# ownduino-metaboard2.net
KiCad netlist of a schematic drawn in EAGLE
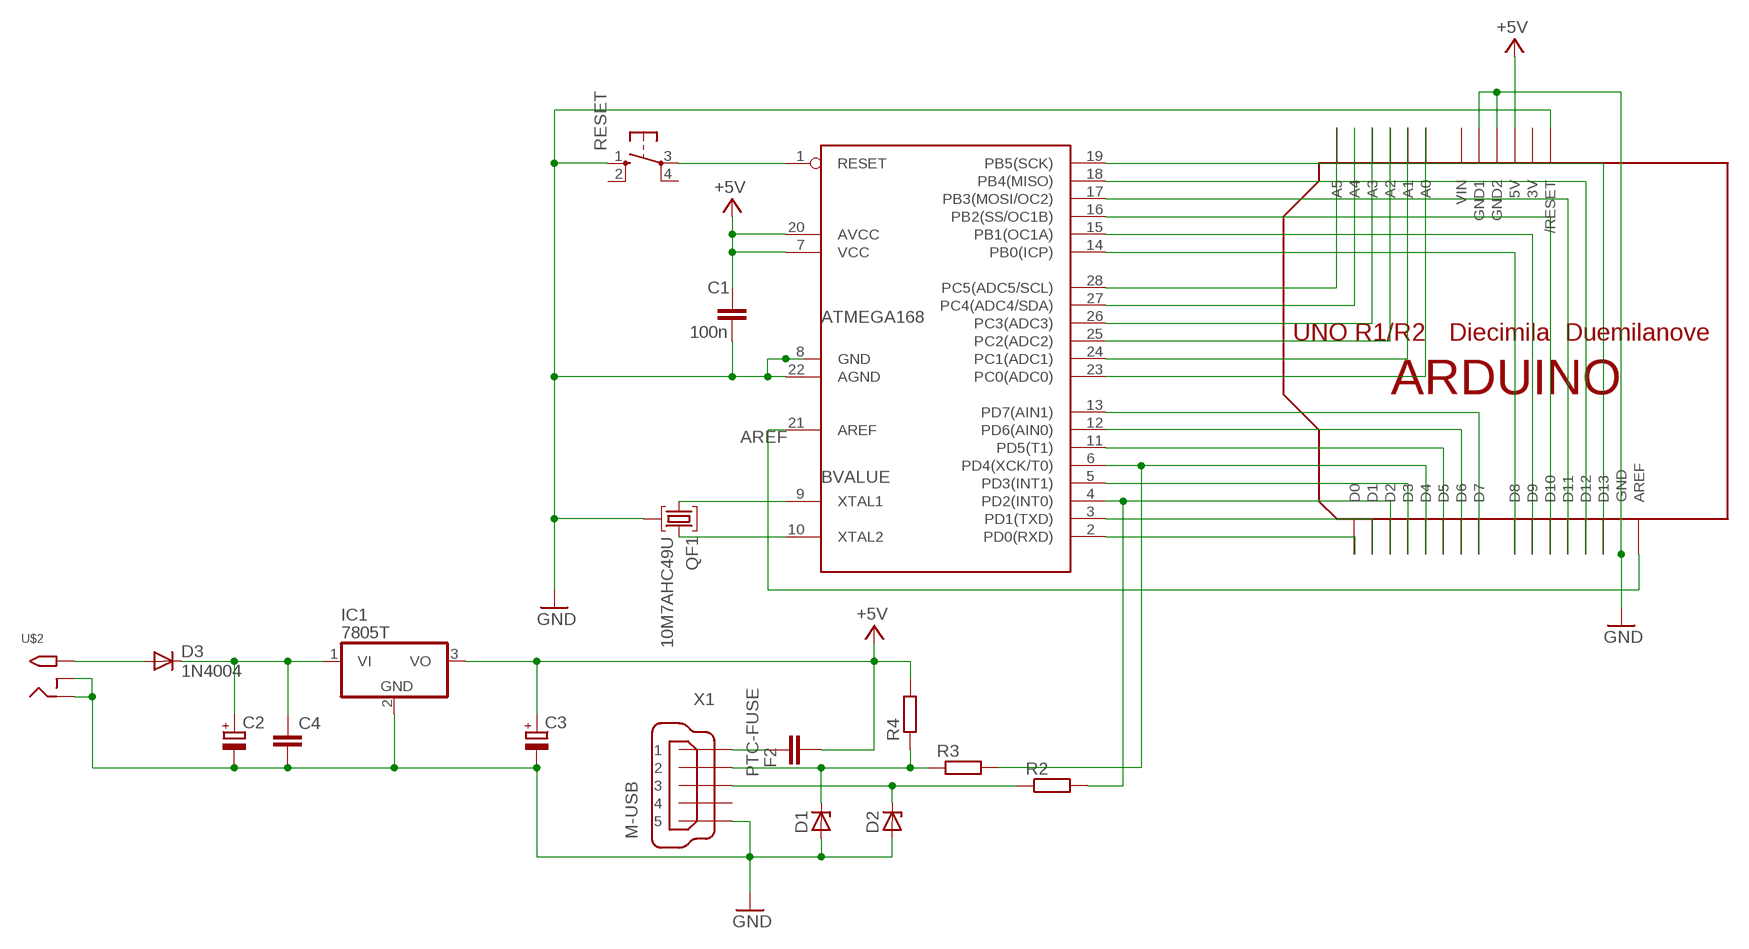
[diagram p0: schematic, sheet 1]

(export (version "E")
  (design (tool "Eeschema 10.0.6"))
  (components
    (comp (ref "BVALUE")
      (value "ATMEGA168")
      (footprint "eagle-import:DIL28-3")
      (libsource (lib "eagle-import") (part "MEGA8-P"))
    )
    (comp (ref "C1")
      (value "100n")
      (footprint "eagle-import:C025-024X044")
      (libsource (lib "eagle-import") (part "C-EU025-024X044"))
    )
    (comp (ref "C2")
      (value "CPOL-EUE5-8.5")
      (footprint "eagle-import:E5-8,5")
      (libsource (lib "eagle-import") (part "CPOL-EUE5-8.5"))
    )
    (comp (ref "C3")
      (value "CPOL-EUE5-8.5")
      (footprint "eagle-import:E5-8,5")
      (libsource (lib "eagle-import") (part "CPOL-EUE5-8.5"))
    )
    (comp (ref "C4")
      (value "C-EU025-025X050")
      (footprint "eagle-import:C025-025X050")
      (libsource (lib "eagle-import") (part "C-EU025-025X050"))
    )
    (comp (ref "D1")
      (value "ZENER-DIODEZD-7.5")
      (footprint "eagle-import:ZDIO-7.5")
      (libsource (lib "eagle-import") (part "ZENER-DIODEZD-7.5"))
    )
    (comp (ref "D2")
      (value "ZENER-DIODEZD-5")
      (footprint "eagle-import:ZDIO-5")
      (libsource (lib "eagle-import") (part "ZENER-DIODEZD-5"))
    )
    (comp (ref "D3")
      (value "1N4004")
      (footprint "eagle-import:DO41-10")
      (libsource (lib "eagle-import") (part "1N4004"))
    )
    (comp (ref "F2")
      (value "PTC-FUSE")
      (footprint "eagle-import:C025_050-025X075")
      (libsource (lib "eagle-import") (part "C-EU025_050-025X075"))
    )
    (comp (ref "IC1")
      (value "7805T")
      (footprint "eagle-import:TO220H")
      (libsource (lib "eagle-import") (part "78T05"))
    )
    (comp (ref "QF1")
      (value "10M7AHC49U")
      (footprint "eagle-import:HC49U")
      (libsource (lib "eagle-import") (part "10MAHC49U7"))
    )
    (comp (ref "R2")
      (value "R-EU_0207/12")
      (footprint "eagle-import:0207_12")
      (libsource (lib "eagle-import") (part "R-EU_0207/12"))
    )
    (comp (ref "R3")
      (value "R-EU_0207/10")
      (footprint "eagle-import:0207_10")
      (libsource (lib "eagle-import") (part "R-EU_0207/10"))
    )
    (comp (ref "R4")
      (value "R-EU_0207/10")
      (footprint "eagle-import:0207_10")
      (libsource (lib "eagle-import") (part "R-EU_0207/10"))
    )
    (comp (ref "RESET")
      (value "10-XX")
      (footprint "eagle-import:B3F-10XX")
      (libsource (lib "eagle-import") (part "10-XX"))
    )
    (comp (ref "U$1")
      (value "ARDUINOUNO")
      (footprint "eagle-import:ARDUINO")
      (libsource (lib "eagle-import") (part "ARDUINOUNO"))
    )
    (comp (ref "U$2")
      (value "2.1MMJACKTHM")
      (footprint "eagle-import:PJ-102A")
      (libsource (lib "eagle-import") (part "2.1MMJACKTHM"))
    )
    (comp (ref "X1")
      (value "M-USB")
      (footprint "eagle-import:32005-601")
      (libsource (lib "eagle-import") (part "MINI-USB_SHIELD5P2-32005-601"))
    )
  )
  (nets
    (net (code "1") (name "+5V") (class "Default")
      (node (ref "BVALUE") (pin "20") (pinfunction "AVCC_20") (pintype "bidirectional"))
      (node (ref "BVALUE") (pin "7") (pinfunction "VCC_7") (pintype "bidirectional"))
      (node (ref "C1") (pin "1") (pinfunction "1_1") (pintype "passive"))
      (node (ref "C3") (pin "+") (pinfunction "+_+") (pintype "passive"))
      (node (ref "F2") (pin "1") (pinfunction "1_1") (pintype "passive"))
      (node (ref "IC1") (pin "3") (pinfunction "VO_3") (pintype "passive"))
      (node (ref "R4") (pin "2") (pinfunction "2_2") (pintype "passive"))
      (node (ref "U$1") (pin "5V") (pinfunction "5V_5V") (pintype "power_in"))
    )
    (net (code "2") (name "/3V") (class "Default")
      (node (ref "U$1") (pin "3V") (pinfunction "3V_3V") (pintype "power_in"))
    )
    (net (code "3") (name "/AREF") (class "Default")
      (node (ref "BVALUE") (pin "21") (pinfunction "AREF_21") (pintype "bidirectional"))
      (node (ref "U$1") (pin "AREF") (pinfunction "AREF_AREF") (pintype "bidirectional"))
    )
    (net (code "4") (name "/VIN") (class "Default")
      (node (ref "U$1") (pin "VIN") (pinfunction "VIN_VIN") (pintype "power_in"))
    )
    (net (code "5") (name "GND") (class "Default")
      (node (ref "BVALUE") (pin "22") (pinfunction "AGND_22") (pintype "bidirectional"))
      (node (ref "BVALUE") (pin "8") (pinfunction "GND_8") (pintype "bidirectional"))
      (node (ref "C1") (pin "2") (pinfunction "2_2") (pintype "passive"))
      (node (ref "C2") (pin "-") (pinfunction "-_-") (pintype "passive"))
      (node (ref "C3") (pin "-") (pinfunction "-_-") (pintype "passive"))
      (node (ref "C4") (pin "2") (pinfunction "2_2") (pintype "passive"))
      (node (ref "D1") (pin "A") (pinfunction "A_A") (pintype "passive"))
      (node (ref "D2") (pin "A") (pinfunction "A_A") (pintype "passive"))
      (node (ref "IC1") (pin "2") (pinfunction "GND_2") (pintype "passive"))
      (node (ref "QF1") (pin "2") (pinfunction "2_2") (pintype "passive"))
      (node (ref "RESET") (pin "1") (pinfunction "S_1") (pintype "passive"))
      (node (ref "U$1") (pin "GND") (pinfunction "GND_GND") (pintype "power_in"))
      (node (ref "U$1") (pin "GND1") (pinfunction "GND1_GND1") (pintype "power_in"))
      (node (ref "U$1") (pin "GND2") (pinfunction "GND2_GND2") (pintype "power_in"))
      (node (ref "U$1") (pin "RESET") (pinfunction "/RESET_RESET") (pintype "bidirectional"))
      (node (ref "U$2") (pin "RING") (pinfunction "RING_RING") (pintype "bidirectional"))
      (node (ref "U$2") (pin "RING_SW") (pinfunction "RING_SW_RING_SW") (pintype "bidirectional"))
      (node (ref "X1") (pin "5") (pinfunction "5_5") (pintype "passive"))
    )
    (net (code "6") (name "Net-(BVALUE-PB0(ICP))") (class "Default")
      (node (ref "BVALUE") (pin "14") (pinfunction "PB0(ICP)_14") (pintype "bidirectional"))
      (node (ref "U$1") (pin "D8") (pinfunction "D8_D8") (pintype "bidirectional"))
    )
    (net (code "7") (name "Net-(BVALUE-PB1(OC1A))") (class "Default")
      (node (ref "BVALUE") (pin "15") (pinfunction "PB1(OC1A)_15") (pintype "bidirectional"))
      (node (ref "U$1") (pin "D9") (pinfunction "D9_D9") (pintype "bidirectional"))
    )
    (net (code "8") (name "Net-(BVALUE-PB2(SS{slash}OC1B))") (class "Default")
      (node (ref "BVALUE") (pin "16") (pinfunction "PB2(SS/OC1B)_16") (pintype "bidirectional"))
      (node (ref "U$1") (pin "D10") (pinfunction "D10_D10") (pintype "bidirectional"))
    )
    (net (code "9") (name "Net-(BVALUE-PB3(MOSI{slash}OC2))") (class "Default")
      (node (ref "BVALUE") (pin "17") (pinfunction "PB3(MOSI/OC2)_17") (pintype "bidirectional"))
      (node (ref "U$1") (pin "D11") (pinfunction "D11_D11") (pintype "bidirectional"))
    )
    (net (code "10") (name "Net-(BVALUE-PB4(MISO))") (class "Default")
      (node (ref "BVALUE") (pin "18") (pinfunction "PB4(MISO)_18") (pintype "bidirectional"))
      (node (ref "U$1") (pin "D12") (pinfunction "D12_D12") (pintype "bidirectional"))
    )
    (net (code "11") (name "Net-(BVALUE-PB5(SCK))") (class "Default")
      (node (ref "BVALUE") (pin "19") (pinfunction "PB5(SCK)_19") (pintype "bidirectional"))
      (node (ref "U$1") (pin "D13") (pinfunction "D13_D13") (pintype "bidirectional"))
    )
    (net (code "12") (name "Net-(BVALUE-PC0(ADC0))") (class "Default")
      (node (ref "BVALUE") (pin "23") (pinfunction "PC0(ADC0)_23") (pintype "bidirectional"))
      (node (ref "U$1") (pin "A0") (pinfunction "A0_A0") (pintype "bidirectional"))
    )
    (net (code "13") (name "Net-(BVALUE-PC1(ADC1))") (class "Default")
      (node (ref "BVALUE") (pin "24") (pinfunction "PC1(ADC1)_24") (pintype "bidirectional"))
      (node (ref "U$1") (pin "A1") (pinfunction "A1_A1") (pintype "bidirectional"))
    )
    (net (code "14") (name "Net-(BVALUE-PC2(ADC2))") (class "Default")
      (node (ref "BVALUE") (pin "25") (pinfunction "PC2(ADC2)_25") (pintype "bidirectional"))
      (node (ref "U$1") (pin "A2") (pinfunction "A2_A2") (pintype "bidirectional"))
    )
    (net (code "15") (name "Net-(BVALUE-PC3(ADC3))") (class "Default")
      (node (ref "BVALUE") (pin "26") (pinfunction "PC3(ADC3)_26") (pintype "bidirectional"))
      (node (ref "U$1") (pin "A3") (pinfunction "A3_A3") (pintype "bidirectional"))
    )
    (net (code "16") (name "Net-(BVALUE-PC4(ADC4{slash}SDA))") (class "Default")
      (node (ref "BVALUE") (pin "27") (pinfunction "PC4(ADC4/SDA)_27") (pintype "bidirectional"))
      (node (ref "U$1") (pin "A4") (pinfunction "A4_A4") (pintype "bidirectional"))
    )
    (net (code "17") (name "Net-(BVALUE-PC5(ADC5{slash}SCL))") (class "Default")
      (node (ref "BVALUE") (pin "28") (pinfunction "PC5(ADC5/SCL)_28") (pintype "bidirectional"))
      (node (ref "U$1") (pin "A5") (pinfunction "A5_A5") (pintype "bidirectional"))
    )
    (net (code "18") (name "Net-(BVALUE-PD0(RXD))") (class "Default")
      (node (ref "BVALUE") (pin "2") (pinfunction "PD0(RXD)_2") (pintype "bidirectional"))
      (node (ref "U$1") (pin "D0") (pinfunction "D0_D0") (pintype "bidirectional"))
    )
    (net (code "19") (name "Net-(BVALUE-PD1(TXD))") (class "Default")
      (node (ref "BVALUE") (pin "3") (pinfunction "PD1(TXD)_3") (pintype "bidirectional"))
      (node (ref "U$1") (pin "D1") (pinfunction "D1_D1") (pintype "bidirectional"))
    )
    (net (code "20") (name "Net-(BVALUE-PD2(INT0))") (class "Default")
      (node (ref "BVALUE") (pin "4") (pinfunction "PD2(INT0)_4") (pintype "bidirectional"))
      (node (ref "R2") (pin "2") (pinfunction "2_2") (pintype "passive"))
      (node (ref "U$1") (pin "D2") (pinfunction "D2_D2") (pintype "bidirectional"))
    )
    (net (code "21") (name "Net-(BVALUE-PD3(INT1))") (class "Default")
      (node (ref "BVALUE") (pin "5") (pinfunction "PD3(INT1)_5") (pintype "bidirectional"))
      (node (ref "U$1") (pin "D3") (pinfunction "D3_D3") (pintype "bidirectional"))
    )
    (net (code "22") (name "Net-(BVALUE-PD4(XCK{slash}T0))") (class "Default")
      (node (ref "BVALUE") (pin "6") (pinfunction "PD4(XCK/T0)_6") (pintype "bidirectional"))
      (node (ref "R3") (pin "2") (pinfunction "2_2") (pintype "passive"))
      (node (ref "U$1") (pin "D4") (pinfunction "D4_D4") (pintype "bidirectional"))
    )
    (net (code "23") (name "Net-(BVALUE-PD5(T1))") (class "Default")
      (node (ref "BVALUE") (pin "11") (pinfunction "PD5(T1)_11") (pintype "bidirectional"))
      (node (ref "U$1") (pin "D5") (pinfunction "D5_D5") (pintype "bidirectional"))
    )
    (net (code "24") (name "Net-(BVALUE-PD6(AIN0))") (class "Default")
      (node (ref "BVALUE") (pin "12") (pinfunction "PD6(AIN0)_12") (pintype "bidirectional"))
      (node (ref "U$1") (pin "D6") (pinfunction "D6_D6") (pintype "bidirectional"))
    )
    (net (code "25") (name "Net-(BVALUE-PD7(AIN1))") (class "Default")
      (node (ref "BVALUE") (pin "13") (pinfunction "PD7(AIN1)_13") (pintype "bidirectional"))
      (node (ref "U$1") (pin "D7") (pinfunction "D7_D7") (pintype "bidirectional"))
    )
    (net (code "26") (name "Net-(BVALUE-RESET)") (class "Default")
      (node (ref "BVALUE") (pin "1") (pinfunction "RESET_1") (pintype "bidirectional"))
      (node (ref "RESET") (pin "3") (pinfunction "P_3") (pintype "passive"))
    )
    (net (code "27") (name "Net-(BVALUE-XTAL1)") (class "Default")
      (node (ref "BVALUE") (pin "9") (pinfunction "XTAL1_9") (pintype "bidirectional"))
      (node (ref "QF1") (pin "1") (pinfunction "1_1") (pintype "passive"))
    )
    (net (code "28") (name "Net-(BVALUE-XTAL2)") (class "Default")
      (node (ref "BVALUE") (pin "10") (pinfunction "XTAL2_10") (pintype "bidirectional"))
      (node (ref "QF1") (pin "3") (pinfunction "3_3") (pintype "passive"))
    )
    (net (code "29") (name "Net-(D1-PadC)") (class "Default")
      (node (ref "D1") (pin "C") (pinfunction "C_C") (pintype "passive"))
      (node (ref "R3") (pin "1") (pinfunction "1_1") (pintype "passive"))
      (node (ref "R4") (pin "1") (pinfunction "1_1") (pintype "passive"))
      (node (ref "X1") (pin "2") (pinfunction "2_2") (pintype "passive"))
    )
    (net (code "30") (name "Net-(D2-PadC)") (class "Default")
      (node (ref "D2") (pin "C") (pinfunction "C_C") (pintype "passive"))
      (node (ref "R2") (pin "1") (pinfunction "1_1") (pintype "passive"))
      (node (ref "X1") (pin "3") (pinfunction "3_3") (pintype "passive"))
    )
    (net (code "31") (name "Net-(D3-PadA)") (class "Default")
      (node (ref "D3") (pin "A") (pinfunction "A_A") (pintype "passive"))
      (node (ref "U$2") (pin "TIP") (pinfunction "TIP_TIP") (pintype "bidirectional"))
    )
    (net (code "32") (name "Net-(F2-Pad2)") (class "Default")
      (node (ref "F2") (pin "2") (pinfunction "2_2") (pintype "passive"))
      (node (ref "X1") (pin "1") (pinfunction "1_1") (pintype "passive"))
    )
    (net (code "33") (name "Net-(IC1-VI)") (class "Default")
      (node (ref "C2") (pin "+") (pinfunction "+_+") (pintype "passive"))
      (node (ref "C4") (pin "1") (pinfunction "1_1") (pintype "passive"))
      (node (ref "D3") (pin "C") (pinfunction "C_C") (pintype "passive"))
      (node (ref "IC1") (pin "1") (pinfunction "VI_1") (pintype "input"))
    )
    (net (code "34") (name "unconnected-(RESET-P1-Pad4)") (class "Default")
      (node (ref "RESET") (pin "4") (pinfunction "P1_4") (pintype "passive"))
    )
    (net (code "35") (name "unconnected-(RESET-S1-Pad2)") (class "Default")
      (node (ref "RESET") (pin "2") (pinfunction "S1_2") (pintype "passive"))
    )
    (net (code "36") (name "unconnected-(X1-Pad4)") (class "Default")
      (node (ref "X1") (pin "4") (pinfunction "4_4") (pintype "passive"))
    )
  )
)
